# 477breakout.net
KiCad netlist of a schematic drawn in EAGLE
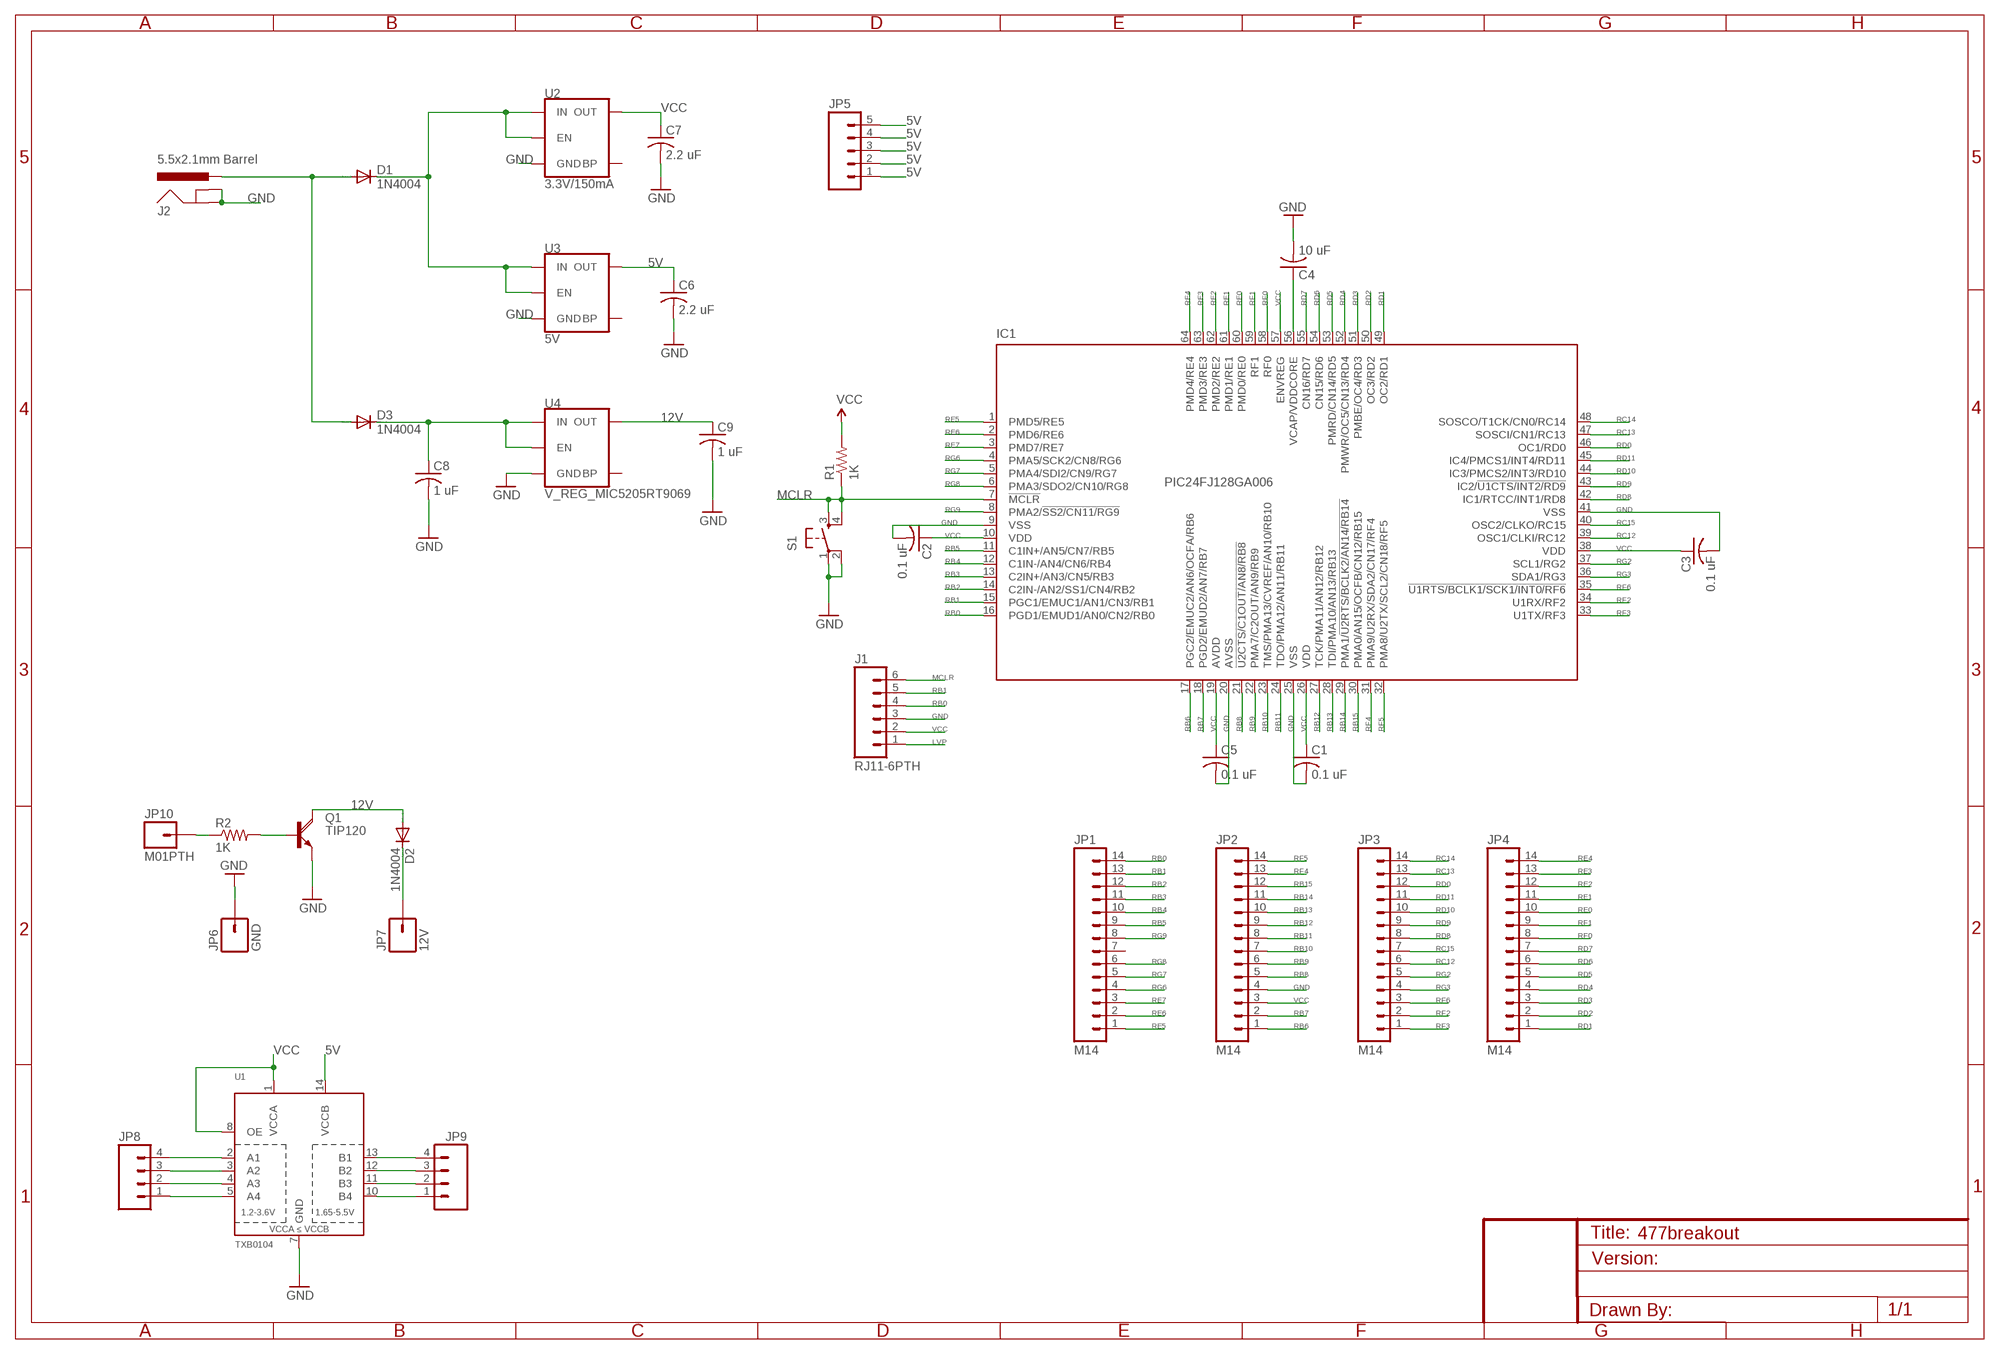
[diagram p0: schematic, sheet 1]

(export (version "E")
  (design (tool "Eeschema 10.0.6"))
  (components
    (comp (ref "C1")
      (value "0.1 uF")
      (footprint "eagle-import:C0402")
      (libsource (lib "eagle-import") (part "C-USC0402"))
    )
    (comp (ref "C2")
      (value "0.1 uF")
      (footprint "eagle-import:C0402")
      (libsource (lib "eagle-import") (part "C-USC0402"))
    )
    (comp (ref "C3")
      (value "0.1 uF")
      (footprint "eagle-import:C0402")
      (libsource (lib "eagle-import") (part "C-USC0402"))
    )
    (comp (ref "C4")
      (value "10 uF")
      (footprint "eagle-import:C0805")
      (libsource (lib "eagle-import") (part "C-USC0805"))
    )
    (comp (ref "C5")
      (value "0.1 uF")
      (footprint "eagle-import:C0402")
      (libsource (lib "eagle-import") (part "C-USC0402"))
    )
    (comp (ref "C6")
      (value "2.2 uF")
      (footprint "eagle-import:C1206")
      (libsource (lib "eagle-import") (part "C-USC1206"))
    )
    (comp (ref "C7")
      (value "2.2 uF")
      (footprint "eagle-import:C1206")
      (libsource (lib "eagle-import") (part "C-USC1206"))
    )
    (comp (ref "C8")
      (value "1 uF")
      (footprint "eagle-import:C0402")
      (libsource (lib "eagle-import") (part "C-USC0402"))
    )
    (comp (ref "C9")
      (value "1 uF")
      (footprint "eagle-import:C0402")
      (libsource (lib "eagle-import") (part "C-USC0402"))
    )
    (comp (ref "D1")
      (value "1N4004")
      (footprint "eagle-import:DO41-10")
      (libsource (lib "eagle-import") (part "1N4004"))
    )
    (comp (ref "D2")
      (value "1N4004")
      (footprint "eagle-import:DO41-10")
      (libsource (lib "eagle-import") (part "1N4004"))
    )
    (comp (ref "D3")
      (value "1N4004")
      (footprint "eagle-import:DO41-10")
      (libsource (lib "eagle-import") (part "1N4004"))
    )
    (comp (ref "IC1")
      (value "PIC24FJ128GA006")
      (footprint "eagle-import:TQFP64-10X10")
      (fields (field (name "MF") "MICROCHIP") (field (name "MPN") "PIC24FJ128GA006-I/PT"))
      (libsource (lib "eagle-import") (part "PIC24FJGA006128"))
    )
    (comp (ref "J1")
      (value "RJ11-6PTH")
      (footprint "eagle-import:RJ11-6")
      (libsource (lib "eagle-import") (part "RJ11-6PTH"))
    )
    (comp (ref "J2")
      (value "5.5x2.1mm Barrel")
      (footprint "eagle-import:POWER_JACK_SMD")
      (libsource (lib "eagle-import") (part "POWER_JACKSMD"))
    )
    (comp (ref "JP1")
      (value "M14")
      (footprint "eagle-import:1X14")
      (libsource (lib "eagle-import") (part "M14"))
    )
    (comp (ref "JP2")
      (value "M14")
      (footprint "eagle-import:1X14")
      (libsource (lib "eagle-import") (part "M14"))
    )
    (comp (ref "JP3")
      (value "M14")
      (footprint "eagle-import:1X14")
      (libsource (lib "eagle-import") (part "M14"))
    )
    (comp (ref "JP4")
      (value "M14")
      (footprint "eagle-import:1X14")
      (libsource (lib "eagle-import") (part "M14"))
    )
    (comp (ref "JP5")
      (value "M05")
      (footprint "eagle-import:1X05")
      (libsource (lib "eagle-import") (part "M05"))
    )
    (comp (ref "JP6")
      (value "GND")
      (footprint "eagle-import:1X01")
      (libsource (lib "eagle-import") (part "M01PTH"))
    )
    (comp (ref "JP7")
      (value "12V")
      (footprint "eagle-import:1X01")
      (libsource (lib "eagle-import") (part "M01PTH"))
    )
    (comp (ref "JP8")
      (value "M04PTH")
      (footprint "eagle-import:1X04")
      (libsource (lib "eagle-import") (part "M04PTH"))
    )
    (comp (ref "JP9")
      (value "M04PTH")
      (footprint "eagle-import:1X04")
      (libsource (lib "eagle-import") (part "M04PTH"))
    )
    (comp (ref "JP10")
      (value "M01PTH")
      (footprint "eagle-import:1X01")
      (libsource (lib "eagle-import") (part "M01PTH"))
    )
    (comp (ref "Q1")
      (value "TIP120")
      (footprint "eagle-import:TO220AH")
      (libsource (lib "eagle-import") (part "TIP120"))
    )
    (comp (ref "R1")
      (value "1K")
      (footprint "eagle-import:0204_7")
      (libsource (lib "eagle-import") (part "R-US_0204/7"))
    )
    (comp (ref "R2")
      (value "1K")
      (footprint "eagle-import:0204_7")
      (libsource (lib "eagle-import") (part "R-US_0204/7"))
    )
    (comp (ref "S1")
      (value "TAC_SWITCHPTH")
      (footprint "eagle-import:TACTILE-PTH")
      (libsource (lib "eagle-import") (part "TAC_SWITCHPTH"))
    )
    (comp (ref "U1")
      (value "TXB0104")
      (footprint "eagle-import:SO14")
      (libsource (lib "eagle-import") (part "TXB0104PWRSOIC14"))
    )
    (comp (ref "U2")
      (value "3.3V/150mA")
      (footprint "eagle-import:SOT23-5")
      (libsource (lib "eagle-import") (part "V_REG_MIC52053.3V"))
    )
    (comp (ref "U3")
      (value "5V")
      (footprint "eagle-import:SOT23-5")
      (libsource (lib "eagle-import") (part "V_REG_MIC52055V"))
    )
    (comp (ref "U4")
      (value "V_REG_MIC5205RT9069")
      (footprint "eagle-import:SOT23-5")
      (libsource (lib "eagle-import") (part "V_REG_MIC5205RT9069"))
    )
  )
  (nets
    (net (code "1") (name "/5V") (class "Default")
      (node (ref "C6") (pin "1") (pinfunction "1_1") (pintype "passive"))
      (node (ref "JP5") (pin "1") (pinfunction "1_1") (pintype "passive"))
      (node (ref "JP5") (pin "2") (pinfunction "2_2") (pintype "passive"))
      (node (ref "JP5") (pin "3") (pinfunction "3_3") (pintype "passive"))
      (node (ref "JP5") (pin "4") (pinfunction "4_4") (pintype "passive"))
      (node (ref "JP5") (pin "5") (pinfunction "5_5") (pintype "passive"))
      (node (ref "U1") (pin "14") (pinfunction "VCCB_14") (pintype "bidirectional"))
      (node (ref "U3") (pin "5") (pinfunction "OUT_5") (pintype "passive"))
    )
    (net (code "2") (name "/12V") (class "Default")
      (node (ref "C9") (pin "1") (pinfunction "1_1") (pintype "passive"))
      (node (ref "D2") (pin "A") (pinfunction "A_A") (pintype "passive"))
      (node (ref "Q1") (pin "C") (pinfunction "C_C") (pintype "passive"))
      (node (ref "U4") (pin "5") (pinfunction "OUT_5") (pintype "passive"))
    )
    (net (code "3") (name "/LVP") (class "Default")
      (node (ref "J1") (pin "1") (pinfunction "1_1") (pintype "passive"))
    )
    (net (code "4") (name "/MCLR") (class "Default")
      (node (ref "IC1") (pin "7") (pinfunction "~{MCLR}_7") (pintype "bidirectional"))
      (node (ref "J1") (pin "6") (pinfunction "6_6") (pintype "passive"))
      (node (ref "R1") (pin "1") (pinfunction "1_1") (pintype "passive"))
      (node (ref "S1") (pin "3") (pinfunction "3_3") (pintype "passive"))
      (node (ref "S1") (pin "4") (pinfunction "4_4") (pintype "passive"))
    )
    (net (code "5") (name "/RB0") (class "Default")
      (node (ref "IC1") (pin "16") (pinfunction "PGD1/EMUD1/AN0/CN2/RB0_16") (pintype "bidirectional"))
      (node (ref "J1") (pin "4") (pinfunction "4_4") (pintype "passive"))
      (node (ref "JP1") (pin "14") (pinfunction "14_14") (pintype "passive"))
    )
    (net (code "6") (name "/RB1") (class "Default")
      (node (ref "IC1") (pin "15") (pinfunction "PGC1/EMUC1/AN1/CN3/RB1_15") (pintype "bidirectional"))
      (node (ref "J1") (pin "5") (pinfunction "5_5") (pintype "passive"))
      (node (ref "JP1") (pin "13") (pinfunction "13_13") (pintype "passive"))
    )
    (net (code "7") (name "/RB2") (class "Default")
      (node (ref "IC1") (pin "14") (pinfunction "C2IN-/AN2/SS1/CN4/RB2_14") (pintype "bidirectional"))
      (node (ref "JP1") (pin "12") (pinfunction "12_12") (pintype "passive"))
    )
    (net (code "8") (name "/RB3") (class "Default")
      (node (ref "IC1") (pin "13") (pinfunction "C2IN+/AN3/CN5/RB3_13") (pintype "bidirectional"))
      (node (ref "JP1") (pin "11") (pinfunction "11_11") (pintype "passive"))
    )
    (net (code "9") (name "/RB4") (class "Default")
      (node (ref "IC1") (pin "12") (pinfunction "C1IN-/AN4/CN6/RB4_12") (pintype "bidirectional"))
      (node (ref "JP1") (pin "10") (pinfunction "10_10") (pintype "passive"))
    )
    (net (code "10") (name "/RB5") (class "Default")
      (node (ref "IC1") (pin "11") (pinfunction "C1IN+/AN5/CN7/RB5_11") (pintype "bidirectional"))
      (node (ref "JP1") (pin "9") (pinfunction "9_9") (pintype "passive"))
    )
    (net (code "11") (name "/RB6") (class "Default")
      (node (ref "IC1") (pin "17") (pinfunction "PGC2/EMUC2/AN6/OCFA/RB6_17") (pintype "bidirectional"))
      (node (ref "JP2") (pin "1") (pinfunction "1_1") (pintype "passive"))
    )
    (net (code "12") (name "/RB7") (class "Default")
      (node (ref "IC1") (pin "18") (pinfunction "PGD2/EMUD2/AN7/RB7_18") (pintype "bidirectional"))
      (node (ref "JP2") (pin "2") (pinfunction "2_2") (pintype "passive"))
    )
    (net (code "13") (name "/RB8") (class "Default")
      (node (ref "IC1") (pin "21") (pinfunction "~{U2CTS/C1OUT/AN8/RB8}_21") (pintype "bidirectional"))
      (node (ref "JP2") (pin "5") (pinfunction "5_5") (pintype "passive"))
    )
    (net (code "14") (name "/RB9") (class "Default")
      (node (ref "IC1") (pin "22") (pinfunction "PMA7/C2OUT/AN9/RB9_22") (pintype "bidirectional"))
      (node (ref "JP2") (pin "6") (pinfunction "6_6") (pintype "passive"))
    )
    (net (code "15") (name "/RB10") (class "Default")
      (node (ref "IC1") (pin "23") (pinfunction "TMS/PMA13/CVREF/AN10/RB10_23") (pintype "bidirectional"))
      (node (ref "JP2") (pin "7") (pinfunction "7_7") (pintype "passive"))
    )
    (net (code "16") (name "/RB11") (class "Default")
      (node (ref "IC1") (pin "24") (pinfunction "TDO/PMA12/AN11/RB11_24") (pintype "bidirectional"))
      (node (ref "JP2") (pin "8") (pinfunction "8_8") (pintype "passive"))
    )
    (net (code "17") (name "/RB12") (class "Default")
      (node (ref "IC1") (pin "27") (pinfunction "TCK/PMA11/AN12/RB12_27") (pintype "bidirectional"))
      (node (ref "JP2") (pin "9") (pinfunction "9_9") (pintype "passive"))
    )
    (net (code "18") (name "/RB13") (class "Default")
      (node (ref "IC1") (pin "28") (pinfunction "TDI/PMA10/AN13/RB13_28") (pintype "bidirectional"))
      (node (ref "JP2") (pin "10") (pinfunction "10_10") (pintype "passive"))
    )
    (net (code "19") (name "/RB14") (class "Default")
      (node (ref "IC1") (pin "29") (pinfunction "PMA1/~{U2RTS/BCLK2/AN14/RB14}_29") (pintype "bidirectional"))
      (node (ref "JP2") (pin "11") (pinfunction "11_11") (pintype "passive"))
    )
    (net (code "20") (name "/RB15") (class "Default")
      (node (ref "IC1") (pin "30") (pinfunction "PMA0/AN15/OCFB/CN12/RB15_30") (pintype "bidirectional"))
      (node (ref "JP2") (pin "12") (pinfunction "12_12") (pintype "passive"))
    )
    (net (code "21") (name "/RC12") (class "Default")
      (node (ref "IC1") (pin "39") (pinfunction "OSC1/CLKI/RC12_39") (pintype "bidirectional"))
      (node (ref "JP3") (pin "6") (pinfunction "6_6") (pintype "passive"))
    )
    (net (code "22") (name "/RC13") (class "Default")
      (node (ref "IC1") (pin "47") (pinfunction "SOSCI/CN1/RC13_47") (pintype "bidirectional"))
      (node (ref "JP3") (pin "13") (pinfunction "13_13") (pintype "passive"))
    )
    (net (code "23") (name "/RC14") (class "Default")
      (node (ref "IC1") (pin "48") (pinfunction "SOSCO/T1CK/CN0/RC14_48") (pintype "bidirectional"))
      (node (ref "JP3") (pin "14") (pinfunction "14_14") (pintype "passive"))
    )
    (net (code "24") (name "/RC15") (class "Default")
      (node (ref "IC1") (pin "40") (pinfunction "OSC2/CLKO/RC15_40") (pintype "bidirectional"))
      (node (ref "JP3") (pin "7") (pinfunction "7_7") (pintype "passive"))
    )
    (net (code "25") (name "/RD0") (class "Default")
      (node (ref "IC1") (pin "46") (pinfunction "OC1/RD0_46") (pintype "bidirectional"))
      (node (ref "JP3") (pin "12") (pinfunction "12_12") (pintype "passive"))
    )
    (net (code "26") (name "/RD1") (class "Default")
      (node (ref "IC1") (pin "49") (pinfunction "OC2/RD1_49") (pintype "bidirectional"))
      (node (ref "JP4") (pin "1") (pinfunction "1_1") (pintype "passive"))
    )
    (net (code "27") (name "/RD2") (class "Default")
      (node (ref "IC1") (pin "50") (pinfunction "OC3/RD2_50") (pintype "bidirectional"))
      (node (ref "JP4") (pin "2") (pinfunction "2_2") (pintype "passive"))
    )
    (net (code "28") (name "/RD3") (class "Default")
      (node (ref "IC1") (pin "51") (pinfunction "PMBE/OC4/RD3_51") (pintype "bidirectional"))
      (node (ref "JP4") (pin "3") (pinfunction "3_3") (pintype "passive"))
    )
    (net (code "29") (name "/RD4") (class "Default")
      (node (ref "IC1") (pin "52") (pinfunction "PMWR/OC5/CN13/RD4_52") (pintype "bidirectional"))
      (node (ref "JP4") (pin "4") (pinfunction "4_4") (pintype "passive"))
    )
    (net (code "30") (name "/RD5") (class "Default")
      (node (ref "IC1") (pin "53") (pinfunction "PMRD/CN14/RD5_53") (pintype "bidirectional"))
      (node (ref "JP4") (pin "5") (pinfunction "5_5") (pintype "passive"))
    )
    (net (code "31") (name "/RD6") (class "Default")
      (node (ref "IC1") (pin "54") (pinfunction "CN15/RD6_54") (pintype "bidirectional"))
      (node (ref "JP4") (pin "6") (pinfunction "6_6") (pintype "passive"))
    )
    (net (code "32") (name "/RD7") (class "Default")
      (node (ref "IC1") (pin "55") (pinfunction "CN16/RD7_55") (pintype "bidirectional"))
      (node (ref "JP4") (pin "7") (pinfunction "7_7") (pintype "passive"))
    )
    (net (code "33") (name "/RD8") (class "Default")
      (node (ref "IC1") (pin "42") (pinfunction "IC1/RTCC/INT1/RD8_42") (pintype "bidirectional"))
      (node (ref "JP3") (pin "8") (pinfunction "8_8") (pintype "passive"))
    )
    (net (code "34") (name "/RD9") (class "Default")
      (node (ref "IC1") (pin "43") (pinfunction "IC2/~{U1CTS/INT2/RD9}_43") (pintype "bidirectional"))
      (node (ref "JP3") (pin "9") (pinfunction "9_9") (pintype "passive"))
    )
    (net (code "35") (name "/RD10") (class "Default")
      (node (ref "IC1") (pin "44") (pinfunction "IC3/PMCS2/INT3/RD10_44") (pintype "bidirectional"))
      (node (ref "JP3") (pin "10") (pinfunction "10_10") (pintype "passive"))
    )
    (net (code "36") (name "/RD11") (class "Default")
      (node (ref "IC1") (pin "45") (pinfunction "IC4/PMCS1/INT4/RD11_45") (pintype "bidirectional"))
      (node (ref "JP3") (pin "11") (pinfunction "11_11") (pintype "passive"))
    )
    (net (code "37") (name "/RE0") (class "Default")
      (node (ref "IC1") (pin "60") (pinfunction "PMD0/RE0_60") (pintype "bidirectional"))
      (node (ref "JP4") (pin "10") (pinfunction "10_10") (pintype "passive"))
    )
    (net (code "38") (name "/RE1") (class "Default")
      (node (ref "IC1") (pin "61") (pinfunction "PMD1/RE1_61") (pintype "bidirectional"))
      (node (ref "JP4") (pin "11") (pinfunction "11_11") (pintype "passive"))
    )
    (net (code "39") (name "/RE2") (class "Default")
      (node (ref "IC1") (pin "62") (pinfunction "PMD2/RE2_62") (pintype "bidirectional"))
      (node (ref "JP4") (pin "12") (pinfunction "12_12") (pintype "passive"))
    )
    (net (code "40") (name "/RE3") (class "Default")
      (node (ref "IC1") (pin "63") (pinfunction "PMD3/RE3_63") (pintype "bidirectional"))
      (node (ref "JP4") (pin "13") (pinfunction "13_13") (pintype "passive"))
    )
    (net (code "41") (name "/RE4") (class "Default")
      (node (ref "IC1") (pin "64") (pinfunction "PMD4/RE4_64") (pintype "bidirectional"))
      (node (ref "JP4") (pin "14") (pinfunction "14_14") (pintype "passive"))
    )
    (net (code "42") (name "/RE5") (class "Default")
      (node (ref "IC1") (pin "1") (pinfunction "PMD5/RE5_1") (pintype "bidirectional"))
      (node (ref "JP1") (pin "1") (pinfunction "1_1") (pintype "passive"))
    )
    (net (code "43") (name "/RE6") (class "Default")
      (node (ref "IC1") (pin "2") (pinfunction "PMD6/RE6_2") (pintype "bidirectional"))
      (node (ref "JP1") (pin "2") (pinfunction "2_2") (pintype "passive"))
    )
    (net (code "44") (name "/RE7") (class "Default")
      (node (ref "IC1") (pin "3") (pinfunction "PMD7/RE7_3") (pintype "bidirectional"))
      (node (ref "JP1") (pin "3") (pinfunction "3_3") (pintype "passive"))
    )
    (net (code "45") (name "/RF0") (class "Default")
      (node (ref "IC1") (pin "58") (pinfunction "RF0_58") (pintype "bidirectional"))
      (node (ref "JP4") (pin "8") (pinfunction "8_8") (pintype "passive"))
    )
    (net (code "46") (name "/RF1") (class "Default")
      (node (ref "IC1") (pin "59") (pinfunction "RF1_59") (pintype "bidirectional"))
      (node (ref "JP4") (pin "9") (pinfunction "9_9") (pintype "passive"))
    )
    (net (code "47") (name "/RF2") (class "Default")
      (node (ref "IC1") (pin "34") (pinfunction "U1RX/RF2_34") (pintype "bidirectional"))
      (node (ref "JP3") (pin "2") (pinfunction "2_2") (pintype "passive"))
    )
    (net (code "48") (name "/RF3") (class "Default")
      (node (ref "IC1") (pin "33") (pinfunction "U1TX/RF3_33") (pintype "bidirectional"))
      (node (ref "JP3") (pin "1") (pinfunction "1_1") (pintype "passive"))
    )
    (net (code "49") (name "/RF4") (class "Default")
      (node (ref "IC1") (pin "31") (pinfunction "PMA9/U2RX/SDA2/CN17/RF4_31") (pintype "bidirectional"))
      (node (ref "JP2") (pin "13") (pinfunction "13_13") (pintype "passive"))
    )
    (net (code "50") (name "/RF5") (class "Default")
      (node (ref "IC1") (pin "32") (pinfunction "PMA8/U2TX/SCL2/CN18/RF5_32") (pintype "bidirectional"))
      (node (ref "JP2") (pin "14") (pinfunction "14_14") (pintype "passive"))
    )
    (net (code "51") (name "/RF6") (class "Default")
      (node (ref "IC1") (pin "35") (pinfunction "~{U1RTS/BCLK1/SCK1/INT0/RF6}_35") (pintype "bidirectional"))
      (node (ref "JP3") (pin "3") (pinfunction "3_3") (pintype "passive"))
    )
    (net (code "52") (name "/RG2") (class "Default")
      (node (ref "IC1") (pin "37") (pinfunction "SCL1/RG2_37") (pintype "bidirectional"))
      (node (ref "JP3") (pin "5") (pinfunction "5_5") (pintype "passive"))
    )
    (net (code "53") (name "/RG3") (class "Default")
      (node (ref "IC1") (pin "36") (pinfunction "SDA1/RG3_36") (pintype "bidirectional"))
      (node (ref "JP3") (pin "4") (pinfunction "4_4") (pintype "passive"))
    )
    (net (code "54") (name "/RG6") (class "Default")
      (node (ref "IC1") (pin "4") (pinfunction "PMA5/SCK2/CN8/RG6_4") (pintype "bidirectional"))
      (node (ref "JP1") (pin "4") (pinfunction "4_4") (pintype "passive"))
    )
    (net (code "55") (name "/RG7") (class "Default")
      (node (ref "IC1") (pin "5") (pinfunction "PMA4/SDI2/CN9/RG7_5") (pintype "bidirectional"))
      (node (ref "JP1") (pin "5") (pinfunction "5_5") (pintype "passive"))
    )
    (net (code "56") (name "/RG8") (class "Default")
      (node (ref "IC1") (pin "6") (pinfunction "PMA3/SDO2/CN10/RG8_6") (pintype "bidirectional"))
      (node (ref "JP1") (pin "6") (pinfunction "6_6") (pintype "passive"))
    )
    (net (code "57") (name "/RG9") (class "Default")
      (node (ref "IC1") (pin "8") (pinfunction "PMA2/~{SS2/CN11/RG9}_8") (pintype "bidirectional"))
      (node (ref "JP1") (pin "8") (pinfunction "8_8") (pintype "passive"))
    )
    (net (code "58") (name "GND") (class "Default")
      (node (ref "C1") (pin "2") (pinfunction "2_2") (pintype "passive"))
      (node (ref "C2") (pin "2") (pinfunction "2_2") (pintype "passive"))
      (node (ref "C3") (pin "2") (pinfunction "2_2") (pintype "passive"))
      (node (ref "C4") (pin "2") (pinfunction "2_2") (pintype "passive"))
      (node (ref "C5") (pin "2") (pinfunction "2_2") (pintype "passive"))
      (node (ref "C6") (pin "2") (pinfunction "2_2") (pintype "passive"))
      (node (ref "C7") (pin "2") (pinfunction "2_2") (pintype "passive"))
      (node (ref "C8") (pin "2") (pinfunction "2_2") (pintype "passive"))
      (node (ref "C9") (pin "2") (pinfunction "2_2") (pintype "passive"))
      (node (ref "IC1") (pin "20") (pinfunction "AVSS_20") (pintype "power_in"))
      (node (ref "IC1") (pin "25") (pinfunction "VSS_25") (pintype "power_in"))
      (node (ref "IC1") (pin "41") (pinfunction "VSS_41") (pintype "power_in"))
      (node (ref "IC1") (pin "9") (pinfunction "VSS_9") (pintype "power_in"))
      (node (ref "J1") (pin "3") (pinfunction "3_3") (pintype "passive"))
      (node (ref "J2") (pin "GND") (pinfunction "GNDBREAK_GND") (pintype "bidirectional"))
      (node (ref "J2") (pin "P$4") (pinfunction "GND_P$4") (pintype "bidirectional"))
      (node (ref "JP2") (pin "4") (pinfunction "4_4") (pintype "passive"))
      (node (ref "JP6") (pin "1") (pinfunction "1_1") (pintype "passive"))
      (node (ref "Q1") (pin "E") (pinfunction "E_E") (pintype "passive"))
      (node (ref "S1") (pin "1") (pinfunction "1_1") (pintype "passive"))
      (node (ref "S1") (pin "2") (pinfunction "2_2") (pintype "passive"))
      (node (ref "U1") (pin "7") (pinfunction "GND_7") (pintype "bidirectional"))
      (node (ref "U2") (pin "2") (pinfunction "GND_2") (pintype "input"))
      (node (ref "U3") (pin "2") (pinfunction "GND_2") (pintype "input"))
      (node (ref "U4") (pin "2") (pinfunction "GND_2") (pintype "input"))
    )
    (net (code "59") (name "Net-(D2-PadC)") (class "Default")
      (node (ref "D2") (pin "C") (pinfunction "C_C") (pintype "passive"))
      (node (ref "JP7") (pin "1") (pinfunction "1_1") (pintype "passive"))
    )
    (net (code "60") (name "Net-(IC1-VCAP{slash}VDDCORE)") (class "Default")
      (node (ref "C4") (pin "1") (pinfunction "1_1") (pintype "passive"))
      (node (ref "IC1") (pin "56") (pinfunction "VCAP/VDDCORE_56") (pintype "bidirectional"))
    )
    (net (code "61") (name "Net-(J2-PWR)") (class "Default")
      (node (ref "D1") (pin "A") (pinfunction "A_A") (pintype "passive"))
      (node (ref "D3") (pin "A") (pinfunction "A_A") (pintype "passive"))
      (node (ref "J2") (pin "VIN0") (pinfunction "PWR_VIN0") (pintype "bidirectional"))
    )
    (net (code "62") (name "Net-(JP10-Pad1)") (class "Default")
      (node (ref "JP10") (pin "1") (pinfunction "1_1") (pintype "passive"))
      (node (ref "R2") (pin "1") (pinfunction "1_1") (pintype "passive"))
    )
    (net (code "63") (name "Net-(Q1-PadB)") (class "Default")
      (node (ref "Q1") (pin "B") (pinfunction "B_B") (pintype "passive"))
      (node (ref "R2") (pin "2") (pinfunction "2_2") (pintype "passive"))
    )
    (net (code "64") (name "Net-(U1-A1)") (class "Default")
      (node (ref "JP8") (pin "4") (pinfunction "4_4") (pintype "passive"))
      (node (ref "U1") (pin "2") (pinfunction "A1_2") (pintype "bidirectional"))
    )
    (net (code "65") (name "Net-(U1-A2)") (class "Default")
      (node (ref "JP8") (pin "3") (pinfunction "3_3") (pintype "passive"))
      (node (ref "U1") (pin "3") (pinfunction "A2_3") (pintype "bidirectional"))
    )
    (net (code "66") (name "Net-(U1-A3)") (class "Default")
      (node (ref "JP8") (pin "2") (pinfunction "2_2") (pintype "passive"))
      (node (ref "U1") (pin "4") (pinfunction "A3_4") (pintype "bidirectional"))
    )
    (net (code "67") (name "Net-(U1-A4)") (class "Default")
      (node (ref "JP8") (pin "1") (pinfunction "1_1") (pintype "passive"))
      (node (ref "U1") (pin "5") (pinfunction "A4_5") (pintype "bidirectional"))
    )
    (net (code "68") (name "Net-(U1-B1)") (class "Default")
      (node (ref "JP9") (pin "4") (pinfunction "4_4") (pintype "passive"))
      (node (ref "U1") (pin "13") (pinfunction "B1_13") (pintype "bidirectional"))
    )
    (net (code "69") (name "Net-(U1-B2)") (class "Default")
      (node (ref "JP9") (pin "3") (pinfunction "3_3") (pintype "passive"))
      (node (ref "U1") (pin "12") (pinfunction "B2_12") (pintype "bidirectional"))
    )
    (net (code "70") (name "Net-(U1-B3)") (class "Default")
      (node (ref "JP9") (pin "2") (pinfunction "2_2") (pintype "passive"))
      (node (ref "U1") (pin "11") (pinfunction "B3_11") (pintype "bidirectional"))
    )
    (net (code "71") (name "Net-(U1-B4)") (class "Default")
      (node (ref "JP9") (pin "1") (pinfunction "1_1") (pintype "passive"))
      (node (ref "U1") (pin "10") (pinfunction "B4_10") (pintype "bidirectional"))
    )
    (net (code "72") (name "Net-(U2-EN)") (class "Default")
      (node (ref "D1") (pin "C") (pinfunction "C_C") (pintype "passive"))
      (node (ref "U2") (pin "1") (pinfunction "IN_1") (pintype "input"))
      (node (ref "U2") (pin "3") (pinfunction "EN_3") (pintype "input"))
      (node (ref "U3") (pin "1") (pinfunction "IN_1") (pintype "input"))
      (node (ref "U3") (pin "3") (pinfunction "EN_3") (pintype "input"))
    )
    (net (code "73") (name "Net-(U4-EN)") (class "Default")
      (node (ref "C8") (pin "1") (pinfunction "1_1") (pintype "passive"))
      (node (ref "D3") (pin "C") (pinfunction "C_C") (pintype "passive"))
      (node (ref "U4") (pin "1") (pinfunction "IN_1") (pintype "input"))
      (node (ref "U4") (pin "4") (pinfunction "EN_4") (pintype "input"))
    )
    (net (code "74") (name "VCC") (class "Default")
      (node (ref "C1") (pin "1") (pinfunction "1_1") (pintype "passive"))
      (node (ref "C2") (pin "1") (pinfunction "1_1") (pintype "passive"))
      (node (ref "C3") (pin "1") (pinfunction "1_1") (pintype "passive"))
      (node (ref "C5") (pin "1") (pinfunction "1_1") (pintype "passive"))
      (node (ref "C7") (pin "1") (pinfunction "1_1") (pintype "passive"))
      (node (ref "IC1") (pin "10") (pinfunction "VDD_10") (pintype "power_in"))
      (node (ref "IC1") (pin "19") (pinfunction "AVDD_19") (pintype "power_in"))
      (node (ref "IC1") (pin "26") (pinfunction "VDD_26") (pintype "power_in"))
      (node (ref "IC1") (pin "38") (pinfunction "VDD_38") (pintype "power_in"))
      (node (ref "IC1") (pin "57") (pinfunction "ENVREG_57") (pintype "bidirectional"))
      (node (ref "J1") (pin "2") (pinfunction "2_2") (pintype "passive"))
      (node (ref "JP2") (pin "3") (pinfunction "3_3") (pintype "passive"))
      (node (ref "R1") (pin "2") (pinfunction "2_2") (pintype "passive"))
      (node (ref "U1") (pin "1") (pinfunction "VCCA_1") (pintype "bidirectional"))
      (node (ref "U1") (pin "8") (pinfunction "OE_8") (pintype "bidirectional"))
      (node (ref "U2") (pin "5") (pinfunction "OUT_5") (pintype "passive"))
    )
    (net (code "75") (name "unconnected-(JP1-Pad7)") (class "Default")
      (node (ref "JP1") (pin "7") (pinfunction "7_7") (pintype "passive"))
    )
    (net (code "76") (name "unconnected-(U2-BP-Pad4)") (class "Default")
      (node (ref "U2") (pin "4") (pinfunction "BP_4") (pintype "input"))
    )
    (net (code "77") (name "unconnected-(U3-BP-Pad4)") (class "Default")
      (node (ref "U3") (pin "4") (pinfunction "BP_4") (pintype "input"))
    )
    (net (code "78") (name "unconnected-(U4-BP-Pad3)") (class "Default")
      (node (ref "U4") (pin "3") (pinfunction "BP_3") (pintype "input"))
    )
  )
)
